# ATmega128RFA1-DevBoard.net
KiCad netlist of a schematic drawn in EAGLE
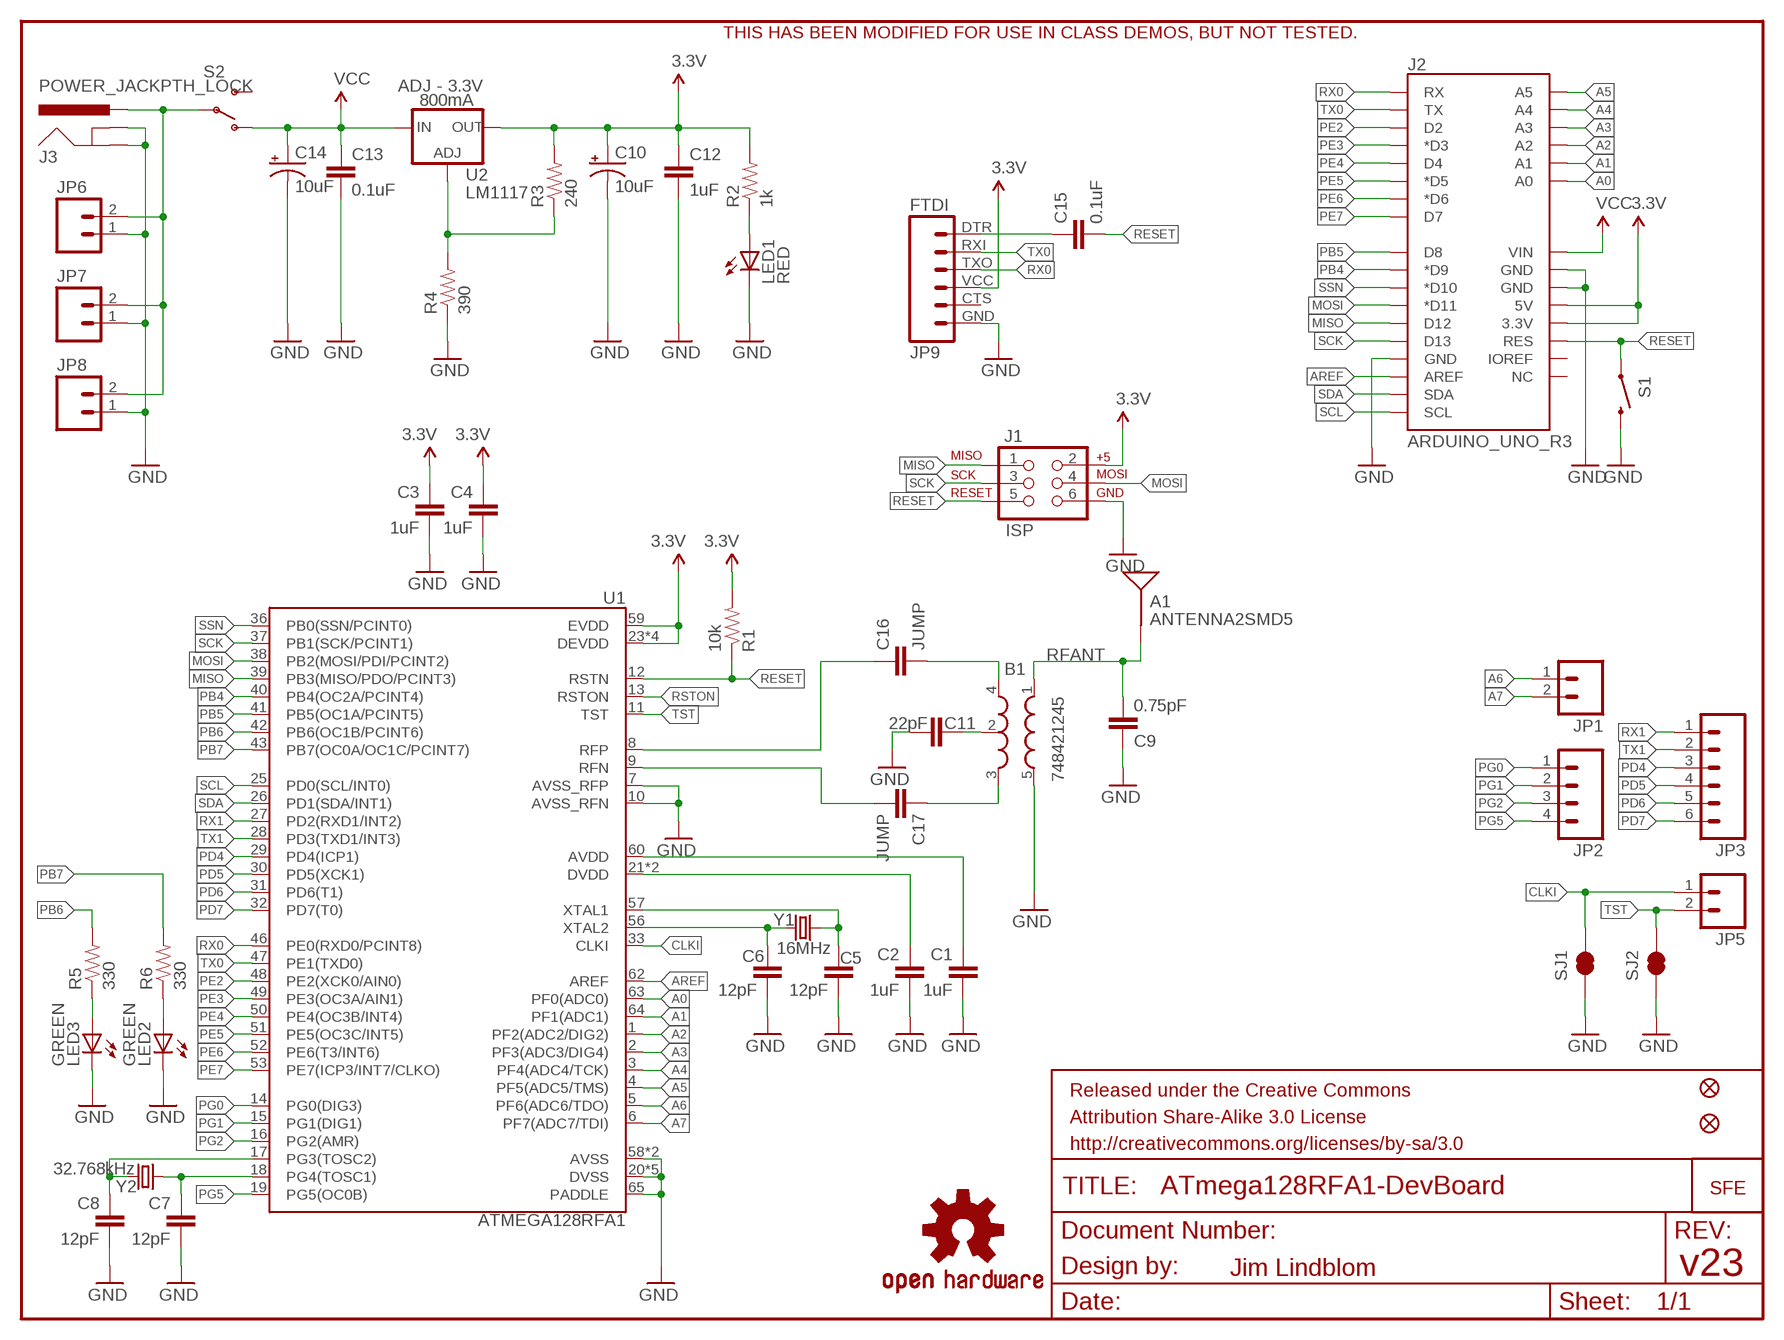
[diagram p0: schematic, sheet 1]

(export (version "E")
  (design (tool "Eeschema 10.0.6"))
  (components
    (comp (ref "A1")
      (value "ANTENNA2SMD5")
      (footprint "eagle-import:ANTENNA-CHIP5")
      (libsource (lib "eagle-import") (part "ANTENNA2SMD5"))
    )
    (comp (ref "B1")
      (value "748421245")
      (footprint "eagle-import:BALUN")
      (libsource (lib "eagle-import") (part "BALUN0805"))
    )
    (comp (ref "C1")
      (value "1uF")
      (footprint "eagle-import:0402-CAP")
      (libsource (lib "eagle-import") (part "CAP0402-CAP"))
    )
    (comp (ref "C2")
      (value "1uF")
      (footprint "eagle-import:0402-CAP")
      (libsource (lib "eagle-import") (part "CAP0402-CAP"))
    )
    (comp (ref "C3")
      (value "1uF")
      (footprint "eagle-import:0402-CAP")
      (libsource (lib "eagle-import") (part "CAP0402-CAP"))
    )
    (comp (ref "C4")
      (value "1uF")
      (footprint "eagle-import:0402-CAP")
      (libsource (lib "eagle-import") (part "CAP0402-CAP"))
    )
    (comp (ref "C5")
      (value "12pF")
      (footprint "eagle-import:0402-CAP")
      (libsource (lib "eagle-import") (part "CAP0402-CAP"))
    )
    (comp (ref "C6")
      (value "12pF")
      (footprint "eagle-import:0402-CAP")
      (libsource (lib "eagle-import") (part "CAP0402-CAP"))
    )
    (comp (ref "C7")
      (value "12pF")
      (footprint "eagle-import:0402-CAP")
      (libsource (lib "eagle-import") (part "CAP0402-CAP"))
    )
    (comp (ref "C8")
      (value "12pF")
      (footprint "eagle-import:0402-CAP")
      (libsource (lib "eagle-import") (part "CAP0402-CAP"))
    )
    (comp (ref "C9")
      (value "0.75pF")
      (footprint "eagle-import:0402-CAP")
      (libsource (lib "eagle-import") (part "CAP0402-CAP"))
    )
    (comp (ref "C10")
      (value "10uF")
      (footprint "eagle-import:EIA3216")
      (libsource (lib "eagle-import") (part "CAP_POL1206"))
    )
    (comp (ref "C11")
      (value "22pF")
      (footprint "eagle-import:0402-CAP")
      (libsource (lib "eagle-import") (part "CAP0402-CAP"))
    )
    (comp (ref "C12")
      (value "1uF")
      (footprint "eagle-import:0402-CAP")
      (libsource (lib "eagle-import") (part "CAP0402-CAP"))
    )
    (comp (ref "C13")
      (value "0.1uF")
      (footprint "eagle-import:0402-CAP")
      (libsource (lib "eagle-import") (part "CAP0402-CAP"))
    )
    (comp (ref "C14")
      (value "10uF")
      (footprint "eagle-import:EIA3216")
      (libsource (lib "eagle-import") (part "CAP_POL1206"))
    )
    (comp (ref "C15")
      (value "0.1uF")
      (footprint "eagle-import:0402-CAP")
      (libsource (lib "eagle-import") (part "CAP0402-CAP"))
    )
    (comp (ref "C16")
      (value "JUMP")
      (footprint "eagle-import:0402-CAP")
      (libsource (lib "eagle-import") (part "CAP0402-CAP"))
    )
    (comp (ref "C17")
      (value "JUMP")
      (footprint "eagle-import:0402-CAP")
      (libsource (lib "eagle-import") (part "CAP0402-CAP"))
    )
    (comp (ref "FID1")
      (value "FIDUCIALUFIDUCIAL")
      (footprint "eagle-import:MICRO-FIDUCIAL")
      (libsource (lib "eagle-import") (part "FIDUCIALUFIDUCIAL"))
    )
    (comp (ref "FID2")
      (value "FIDUCIALUFIDUCIAL")
      (footprint "eagle-import:MICRO-FIDUCIAL")
      (libsource (lib "eagle-import") (part "FIDUCIALUFIDUCIAL"))
    )
    (comp (ref "J1")
      (value "ISP")
      (footprint "eagle-import:2X3-NS")
      (libsource (lib "eagle-import") (part "AVR_SPI_PRG_6NS"))
    )
    (comp (ref "J2")
      (value "ARDUINO_UNO_R3")
      (footprint "eagle-import:ARDUINO_UNO_R3")
      (libsource (lib "eagle-import") (part "ARDUINO_UNO_R3"))
    )
    (comp (ref "J3")
      (value "POWER_JACKPTH_LOCK")
      (footprint "eagle-import:POWER_JACK_PTH_LOCK")
      (libsource (lib "eagle-import") (part "POWER_JACKPTH_LOCK"))
    )
    (comp (ref "JP1")
      (value "M021X02_NO_SILK")
      (footprint "eagle-import:1X02_NO_SILK")
      (libsource (lib "eagle-import") (part "M021X02_NO_SILK"))
    )
    (comp (ref "JP2")
      (value "M041X04_NO_SILK")
      (footprint "eagle-import:1X04_NO_SILK")
      (libsource (lib "eagle-import") (part "M041X04_NO_SILK"))
    )
    (comp (ref "JP3")
      (value "M06SIP-NS")
      (footprint "eagle-import:1X06_NS")
      (libsource (lib "eagle-import") (part "M06SIP-NS"))
    )
    (comp (ref "JP4")
      (value "LOGO-SFENEW")
      (footprint "eagle-import:SFE-NEW-WEBLOGO")
      (libsource (lib "eagle-import") (part "LOGO-SFENEW"))
    )
    (comp (ref "JP5")
      (value "M021X02_NO_SILK")
      (footprint "eagle-import:1X02_NO_SILK")
      (libsource (lib "eagle-import") (part "M021X02_NO_SILK"))
    )
    (comp (ref "JP6")
      (value "M02JST-PTH-2")
      (footprint "eagle-import:JST-2-PTH")
      (libsource (lib "eagle-import") (part "M02JST-PTH-2"))
    )
    (comp (ref "JP7")
      (value "M021X02_NO_SILK")
      (footprint "eagle-import:1X02_NO_SILK")
      (libsource (lib "eagle-import") (part "M021X02_NO_SILK"))
    )
    (comp (ref "JP8")
      (value "M023.5MM-NO_SILK")
      (footprint "eagle-import:SCREWTERMINAL-3.5MM-2-NS")
      (libsource (lib "eagle-import") (part "M023.5MM-NO_SILK"))
    )
    (comp (ref "JP9")
      (value "FTDI")
      (footprint "eagle-import:FTDI_BASIC")
      (libsource (lib "eagle-import") (part "FTDI_BASICPTH"))
    )
    (comp (ref "LED1")
      (value "RED")
      (footprint "eagle-import:LED-0603")
      (libsource (lib "eagle-import") (part "LED0603"))
    )
    (comp (ref "LED2")
      (value "GREEN")
      (footprint "eagle-import:LED-0603")
      (libsource (lib "eagle-import") (part "LED0603"))
    )
    (comp (ref "LED3")
      (value "GREEN")
      (footprint "eagle-import:LED-0603")
      (libsource (lib "eagle-import") (part "LED0603"))
    )
    (comp (ref "R1")
      (value "10k")
      (footprint "eagle-import:0402-RES")
      (libsource (lib "eagle-import") (part "RESISTOR0402-RES"))
    )
    (comp (ref "R2")
      (value "1k")
      (footprint "eagle-import:0402-RES")
      (libsource (lib "eagle-import") (part "RESISTOR0402-RES"))
    )
    (comp (ref "R3")
      (value "240")
      (footprint "eagle-import:0402-RES")
      (libsource (lib "eagle-import") (part "RESISTOR0402-RES"))
    )
    (comp (ref "R4")
      (value "390")
      (footprint "eagle-import:0402-RES")
      (libsource (lib "eagle-import") (part "RESISTOR0402-RES"))
    )
    (comp (ref "R5")
      (value "330")
      (footprint "eagle-import:0402-RES")
      (libsource (lib "eagle-import") (part "RESISTOR0402-RES"))
    )
    (comp (ref "R6")
      (value "330")
      (footprint "eagle-import:0402-RES")
      (libsource (lib "eagle-import") (part "RESISTOR0402-RES"))
    )
    (comp (ref "S1")
      (value "SWITCH-MOMENTARY-2SMD")
      (footprint "eagle-import:TACTILE_SWITCH_SMD")
      (libsource (lib "eagle-import") (part "SWITCH-MOMENTARY-2SMD"))
    )
    (comp (ref "S2")
      (value "SWITCH-SPST-SMD-A")
      (footprint "eagle-import:SWITCH-SPST-SMD-A")
      (libsource (lib "eagle-import") (part "SWITCH-SPST-SMD-A"))
    )
    (comp (ref "SJ1")
      (value "SOLDERJUMPERTRACE")
      (footprint "eagle-import:SJ_2S-TRACE")
      (libsource (lib "eagle-import") (part "SOLDERJUMPERTRACE"))
    )
    (comp (ref "SJ2")
      (value "SOLDERJUMPERTRACE")
      (footprint "eagle-import:SJ_2S-TRACE")
      (libsource (lib "eagle-import") (part "SOLDERJUMPERTRACE"))
    )
    (comp (ref "U$1")
      (value "OSHW-LOGOS")
      (footprint "eagle-import:OSHW-LOGO-S")
      (libsource (lib "eagle-import") (part "OSHW-LOGOS"))
    )
    (comp (ref "U1")
      (value "ATMEGA128RFA1")
      (footprint "eagle-import:QFN-64")
      (libsource (lib "eagle-import") (part "ATMEGA128RFA1"))
    )
    (comp (ref "U2")
      (value "LM1117")
      (footprint "eagle-import:SOT223")
      (libsource (lib "eagle-import") (part "V_REG_317SMD"))
    )
    (comp (ref "Y1")
      (value "16MHz")
      (footprint "eagle-import:CRYSTAL-SMD-5X3")
      (libsource (lib "eagle-import") (part "CRYSTAL5X3"))
    )
    (comp (ref "Y2")
      (value "32.768kHz")
      (footprint "eagle-import:CRYSTAL-32KHZ-SMD")
      (libsource (lib "eagle-import") (part "CRYSTAL32-SMD"))
    )
  )
  (nets
    (net (code "1") (name "/RFANT") (class "Default")
      (node (ref "A1") (pin "FEED") (pinfunction "SIGNAL_FEED") (pintype "bidirectional"))
      (node (ref "B1") (pin "1") (pinfunction "IN_1") (pintype "bidirectional"))
      (node (ref "C9") (pin "2") (pinfunction "2_2") (pintype "passive"))
    )
    (net (code "2") (name "3.3V") (class "Default")
      (node (ref "C10") (pin "A") (pinfunction "+_A") (pintype "passive"))
      (node (ref "C12") (pin "1") (pinfunction "1_1") (pintype "passive"))
      (node (ref "C3") (pin "1") (pinfunction "1_1") (pintype "passive"))
      (node (ref "C4") (pin "1") (pinfunction "1_1") (pintype "passive"))
      (node (ref "J1") (pin "2") (pinfunction "2_2") (pintype "passive"))
      (node (ref "J2") (pin "3.3V") (pinfunction "3.3V_3.3V") (pintype "bidirectional"))
      (node (ref "J2") (pin "5V") (pinfunction "5V_5V") (pintype "bidirectional"))
      (node (ref "JP9") (pin "VCC") (pinfunction "4_VCC") (pintype "passive"))
      (node (ref "R1") (pin "2") (pinfunction "2_2") (pintype "passive"))
      (node (ref "R2") (pin "2") (pinfunction "2_2") (pintype "passive"))
      (node (ref "R3") (pin "2") (pinfunction "2_2") (pintype "passive"))
      (node (ref "U1") (pin "23") (pinfunction "DEVDD_23") (pintype "bidirectional"))
      (node (ref "U1") (pin "34") (pinfunction "DEVDD_34") (pintype "bidirectional"))
      (node (ref "U1") (pin "44") (pinfunction "DEVDD_44") (pintype "bidirectional"))
      (node (ref "U1") (pin "54") (pinfunction "DEVDD_54") (pintype "bidirectional"))
      (node (ref "U1") (pin "59") (pinfunction "EVDD_59") (pintype "bidirectional"))
      (node (ref "U2") (pin "2") (pinfunction "OUT_2") (pintype "output"))
    )
    (net (code "3") (name "A0") (class "Default")
      (node (ref "J2") (pin "A0") (pinfunction "A0_A0") (pintype "bidirectional"))
      (node (ref "U1") (pin "63") (pinfunction "PF0(ADC0)_63") (pintype "bidirectional"))
    )
    (net (code "4") (name "A1") (class "Default")
      (node (ref "J2") (pin "A1") (pinfunction "A1_A1") (pintype "bidirectional"))
      (node (ref "U1") (pin "64") (pinfunction "PF1(ADC1)_64") (pintype "bidirectional"))
    )
    (net (code "5") (name "A2") (class "Default")
      (node (ref "J2") (pin "A2") (pinfunction "A2_A2") (pintype "bidirectional"))
      (node (ref "U1") (pin "1") (pinfunction "PF2(ADC2/DIG2)_1") (pintype "bidirectional"))
    )
    (net (code "6") (name "A3") (class "Default")
      (node (ref "J2") (pin "A3") (pinfunction "A3_A3") (pintype "bidirectional"))
      (node (ref "U1") (pin "2") (pinfunction "PF3(ADC3/DIG4)_2") (pintype "bidirectional"))
    )
    (net (code "7") (name "A4") (class "Default")
      (node (ref "J2") (pin "A4") (pinfunction "A4_A4") (pintype "bidirectional"))
      (node (ref "U1") (pin "3") (pinfunction "PF4(ADC4/TCK)_3") (pintype "bidirectional"))
    )
    (net (code "8") (name "A5") (class "Default")
      (node (ref "J2") (pin "A5") (pinfunction "A5_A5") (pintype "bidirectional"))
      (node (ref "U1") (pin "4") (pinfunction "PF5(ADC5/TMS)_4") (pintype "bidirectional"))
    )
    (net (code "9") (name "A6") (class "Default")
      (node (ref "JP1") (pin "1") (pinfunction "1_1") (pintype "passive"))
      (node (ref "U1") (pin "5") (pinfunction "PF6(ADC6/TDO)_5") (pintype "bidirectional"))
    )
    (net (code "10") (name "A7") (class "Default")
      (node (ref "JP1") (pin "2") (pinfunction "2_2") (pintype "passive"))
      (node (ref "U1") (pin "6") (pinfunction "PF7(ADC7/TDI)_6") (pintype "bidirectional"))
    )
    (net (code "11") (name "AREF") (class "Default")
      (node (ref "J2") (pin "AREF") (pinfunction "AREF_AREF") (pintype "bidirectional"))
      (node (ref "U1") (pin "62") (pinfunction "AREF_62") (pintype "bidirectional"))
    )
    (net (code "12") (name "CLKI") (class "Default")
      (node (ref "JP5") (pin "1") (pinfunction "1_1") (pintype "passive"))
      (node (ref "SJ1") (pin "2") (pinfunction "2_2") (pintype "passive"))
      (node (ref "U1") (pin "33") (pinfunction "CLKI_33") (pintype "bidirectional"))
    )
    (net (code "13") (name "GND") (class "Default")
      (node (ref "B1") (pin "5") (pinfunction "GND_5") (pintype "bidirectional"))
      (node (ref "C1") (pin "2") (pinfunction "2_2") (pintype "passive"))
      (node (ref "C10") (pin "C") (pinfunction "-_C") (pintype "passive"))
      (node (ref "C11") (pin "2") (pinfunction "2_2") (pintype "passive"))
      (node (ref "C12") (pin "2") (pinfunction "2_2") (pintype "passive"))
      (node (ref "C13") (pin "2") (pinfunction "2_2") (pintype "passive"))
      (node (ref "C14") (pin "C") (pinfunction "-_C") (pintype "passive"))
      (node (ref "C2") (pin "2") (pinfunction "2_2") (pintype "passive"))
      (node (ref "C3") (pin "2") (pinfunction "2_2") (pintype "passive"))
      (node (ref "C4") (pin "2") (pinfunction "2_2") (pintype "passive"))
      (node (ref "C5") (pin "2") (pinfunction "2_2") (pintype "passive"))
      (node (ref "C6") (pin "2") (pinfunction "2_2") (pintype "passive"))
      (node (ref "C7") (pin "2") (pinfunction "2_2") (pintype "passive"))
      (node (ref "C8") (pin "2") (pinfunction "2_2") (pintype "passive"))
      (node (ref "C9") (pin "1") (pinfunction "1_1") (pintype "passive"))
      (node (ref "J1") (pin "6") (pinfunction "6_6") (pintype "passive"))
      (node (ref "J2") (pin "GND@0") (pinfunction "GND_GND@0") (pintype "bidirectional"))
      (node (ref "J2") (pin "GND@1") (pinfunction "GND_GND@1") (pintype "bidirectional"))
      (node (ref "J2") (pin "GND@2") (pinfunction "GND_GND@2") (pintype "bidirectional"))
      (node (ref "J3") (pin "GND") (pinfunction "GND_GND") (pintype "bidirectional"))
      (node (ref "J3") (pin "GNDBREAK") (pinfunction "GNDBREAK_GNDBREAK") (pintype "bidirectional"))
      (node (ref "JP6") (pin "1") (pinfunction "1_1") (pintype "passive"))
      (node (ref "JP7") (pin "1") (pinfunction "1_1") (pintype "passive"))
      (node (ref "JP8") (pin "1") (pinfunction "1_1") (pintype "passive"))
      (node (ref "JP9") (pin "GND") (pinfunction "6_GND") (pintype "passive"))
      (node (ref "LED1") (pin "C") (pinfunction "C_C") (pintype "passive"))
      (node (ref "LED2") (pin "C") (pinfunction "C_C") (pintype "passive"))
      (node (ref "LED3") (pin "C") (pinfunction "C_C") (pintype "passive"))
      (node (ref "R4") (pin "1") (pinfunction "1_1") (pintype "passive"))
      (node (ref "S1") (pin "3") (pinfunction "2_3") (pintype "passive"))
      (node (ref "SJ1") (pin "1") (pinfunction "1_1") (pintype "passive"))
      (node (ref "SJ2") (pin "1") (pinfunction "1_1") (pintype "passive"))
      (node (ref "U1") (pin "10") (pinfunction "AVSS_RFN_10") (pintype "bidirectional"))
      (node (ref "U1") (pin "20") (pinfunction "DVSS_20") (pintype "bidirectional"))
      (node (ref "U1") (pin "24") (pinfunction "DVSS_24") (pintype "bidirectional"))
      (node (ref "U1") (pin "35") (pinfunction "DVSS_35") (pintype "bidirectional"))
      (node (ref "U1") (pin "45") (pinfunction "DVSS_45") (pintype "bidirectional"))
      (node (ref "U1") (pin "55") (pinfunction "DVSS_55") (pintype "bidirectional"))
      (node (ref "U1") (pin "58") (pinfunction "AVSS_58") (pintype "bidirectional"))
      (node (ref "U1") (pin "61") (pinfunction "AVSS_61") (pintype "bidirectional"))
      (node (ref "U1") (pin "65") (pinfunction "PADDLE_65") (pintype "bidirectional"))
      (node (ref "U1") (pin "7") (pinfunction "AVSS_RFP_7") (pintype "bidirectional"))
    )
    (net (code "14") (name "MISO") (class "Default")
      (node (ref "J1") (pin "1") (pinfunction "1_1") (pintype "passive"))
      (node (ref "J2") (pin "D12") (pinfunction "D12_D12") (pintype "bidirectional"))
      (node (ref "U1") (pin "39") (pinfunction "PB3(MISO/PDO/PCINT3)_39") (pintype "bidirectional"))
    )
    (net (code "15") (name "MOSI") (class "Default")
      (node (ref "J1") (pin "4") (pinfunction "4_4") (pintype "passive"))
      (node (ref "J2") (pin "D11") (pinfunction "*D11_D11") (pintype "bidirectional"))
      (node (ref "U1") (pin "38") (pinfunction "PB2(MOSI/PDI/PCINT2)_38") (pintype "bidirectional"))
    )
    (net (code "16") (name "Net-(B1-GND-Pad2)") (class "Default")
      (node (ref "B1") (pin "2") (pinfunction "GND_2") (pintype "bidirectional"))
      (node (ref "C11") (pin "1") (pinfunction "1_1") (pintype "passive"))
    )
    (net (code "17") (name "Net-(B1-OUT1)") (class "Default")
      (node (ref "B1") (pin "4") (pinfunction "OUT1_4") (pintype "bidirectional"))
      (node (ref "C16") (pin "2") (pinfunction "2_2") (pintype "passive"))
    )
    (net (code "18") (name "Net-(B1-OUT2)") (class "Default")
      (node (ref "B1") (pin "3") (pinfunction "OUT2_3") (pintype "bidirectional"))
      (node (ref "C17") (pin "1") (pinfunction "1_1") (pintype "passive"))
    )
    (net (code "19") (name "Net-(C2-Pad1)") (class "Default")
      (node (ref "C2") (pin "1") (pinfunction "1_1") (pintype "passive"))
      (node (ref "U1") (pin "21") (pinfunction "DVDD_21") (pintype "bidirectional"))
      (node (ref "U1") (pin "22") (pinfunction "DVDD_22") (pintype "bidirectional"))
    )
    (net (code "20") (name "Net-(JP9-1)") (class "Default")
      (node (ref "C15") (pin "1") (pinfunction "1_1") (pintype "passive"))
      (node (ref "JP9") (pin "DTR") (pinfunction "1_DTR") (pintype "passive"))
    )
    (net (code "21") (name "Net-(LED1-PadA)") (class "Default")
      (node (ref "LED1") (pin "A") (pinfunction "A_A") (pintype "passive"))
      (node (ref "R2") (pin "1") (pinfunction "1_1") (pintype "passive"))
    )
    (net (code "22") (name "Net-(LED2-PadA)") (class "Default")
      (node (ref "LED2") (pin "A") (pinfunction "A_A") (pintype "passive"))
      (node (ref "R6") (pin "1") (pinfunction "1_1") (pintype "passive"))
    )
    (net (code "23") (name "Net-(LED3-PadA)") (class "Default")
      (node (ref "LED3") (pin "A") (pinfunction "A_A") (pintype "passive"))
      (node (ref "R5") (pin "1") (pinfunction "1_1") (pintype "passive"))
    )
    (net (code "24") (name "Net-(S2-P)") (class "Default")
      (node (ref "J3") (pin "PWR") (pinfunction "PWR_PWR") (pintype "bidirectional"))
      (node (ref "JP6") (pin "2") (pinfunction "2_2") (pintype "passive"))
      (node (ref "JP7") (pin "2") (pinfunction "2_2") (pintype "passive"))
      (node (ref "JP8") (pin "2") (pinfunction "2_2") (pintype "passive"))
      (node (ref "S2") (pin "2") (pinfunction "P_2") (pintype "passive"))
    )
    (net (code "25") (name "Net-(U1-AVDD)") (class "Default")
      (node (ref "C1") (pin "1") (pinfunction "1_1") (pintype "passive"))
      (node (ref "U1") (pin "60") (pinfunction "AVDD_60") (pintype "bidirectional"))
    )
    (net (code "26") (name "Net-(U1-PG3(TOSC2))") (class "Default")
      (node (ref "C8") (pin "1") (pinfunction "1_1") (pintype "passive"))
      (node (ref "U1") (pin "17") (pinfunction "PG3(TOSC2)_17") (pintype "bidirectional"))
      (node (ref "Y2") (pin "X2") (pinfunction "2_X2") (pintype "passive"))
    )
    (net (code "27") (name "Net-(U1-PG4(TOSC1))") (class "Default")
      (node (ref "C7") (pin "1") (pinfunction "1_1") (pintype "passive"))
      (node (ref "U1") (pin "18") (pinfunction "PG4(TOSC1)_18") (pintype "bidirectional"))
      (node (ref "Y2") (pin "X1") (pinfunction "1_X1") (pintype "passive"))
    )
    (net (code "28") (name "Net-(U1-RFN)") (class "Default")
      (node (ref "C17") (pin "2") (pinfunction "2_2") (pintype "passive"))
      (node (ref "U1") (pin "9") (pinfunction "RFN_9") (pintype "bidirectional"))
    )
    (net (code "29") (name "Net-(U1-RFP)") (class "Default")
      (node (ref "C16") (pin "1") (pinfunction "1_1") (pintype "passive"))
      (node (ref "U1") (pin "8") (pinfunction "RFP_8") (pintype "bidirectional"))
    )
    (net (code "30") (name "Net-(U1-XTAL1)") (class "Default")
      (node (ref "C5") (pin "1") (pinfunction "1_1") (pintype "passive"))
      (node (ref "U1") (pin "57") (pinfunction "XTAL1_57") (pintype "bidirectional"))
      (node (ref "Y1") (pin "3") (pinfunction "2_3") (pintype "passive"))
    )
    (net (code "31") (name "Net-(U1-XTAL2)") (class "Default")
      (node (ref "C6") (pin "1") (pinfunction "1_1") (pintype "passive"))
      (node (ref "U1") (pin "56") (pinfunction "XTAL2_56") (pintype "bidirectional"))
      (node (ref "Y1") (pin "1") (pinfunction "1_1") (pintype "passive"))
    )
    (net (code "32") (name "Net-(U2-ADJ)") (class "Default")
      (node (ref "R3") (pin "1") (pinfunction "1_1") (pintype "passive"))
      (node (ref "R4") (pin "2") (pinfunction "2_2") (pintype "passive"))
      (node (ref "U2") (pin "1") (pinfunction "ADJ_1") (pintype "input"))
    )
    (net (code "33") (name "PB4") (class "Default")
      (node (ref "J2") (pin "D9") (pinfunction "*D9_D9") (pintype "bidirectional"))
      (node (ref "U1") (pin "40") (pinfunction "PB4(OC2A/PCINT4)_40") (pintype "bidirectional"))
    )
    (net (code "34") (name "PB5") (class "Default")
      (node (ref "J2") (pin "D8") (pinfunction "D8_D8") (pintype "bidirectional"))
      (node (ref "U1") (pin "41") (pinfunction "PB5(OC1A/PCINT5)_41") (pintype "bidirectional"))
    )
    (net (code "35") (name "PB6") (class "Default")
      (node (ref "R5") (pin "2") (pinfunction "2_2") (pintype "passive"))
      (node (ref "U1") (pin "42") (pinfunction "PB6(OC1B/PCINT6)_42") (pintype "bidirectional"))
    )
    (net (code "36") (name "PB7") (class "Default")
      (node (ref "R6") (pin "2") (pinfunction "2_2") (pintype "passive"))
      (node (ref "U1") (pin "43") (pinfunction "PB7(OC0A/OC1C/PCINT7)_43") (pintype "bidirectional"))
    )
    (net (code "37") (name "PD4") (class "Default")
      (node (ref "JP3") (pin "3") (pinfunction "3_3") (pintype "passive"))
      (node (ref "U1") (pin "29") (pinfunction "PD4(ICP1)_29") (pintype "bidirectional"))
    )
    (net (code "38") (name "PD5") (class "Default")
      (node (ref "JP3") (pin "4") (pinfunction "4_4") (pintype "passive"))
      (node (ref "U1") (pin "30") (pinfunction "PD5(XCK1)_30") (pintype "bidirectional"))
    )
    (net (code "39") (name "PD6") (class "Default")
      (node (ref "JP3") (pin "5") (pinfunction "5_5") (pintype "passive"))
      (node (ref "U1") (pin "31") (pinfunction "PD6(T1)_31") (pintype "bidirectional"))
    )
    (net (code "40") (name "PD7") (class "Default")
      (node (ref "JP3") (pin "6") (pinfunction "6_6") (pintype "passive"))
      (node (ref "U1") (pin "32") (pinfunction "PD7(T0)_32") (pintype "bidirectional"))
    )
    (net (code "41") (name "PE2") (class "Default")
      (node (ref "J2") (pin "D2") (pinfunction "D2_D2") (pintype "bidirectional"))
      (node (ref "U1") (pin "48") (pinfunction "PE2(XCK0/AIN0)_48") (pintype "bidirectional"))
    )
    (net (code "42") (name "PE3") (class "Default")
      (node (ref "J2") (pin "D3") (pinfunction "*D3_D3") (pintype "bidirectional"))
      (node (ref "U1") (pin "49") (pinfunction "PE3(OC3A/AIN1)_49") (pintype "bidirectional"))
    )
    (net (code "43") (name "PE4") (class "Default")
      (node (ref "J2") (pin "D4") (pinfunction "D4_D4") (pintype "bidirectional"))
      (node (ref "U1") (pin "50") (pinfunction "PE4(OC3B/INT4)_50") (pintype "bidirectional"))
    )
    (net (code "44") (name "PE5") (class "Default")
      (node (ref "J2") (pin "D5") (pinfunction "*D5_D5") (pintype "bidirectional"))
      (node (ref "U1") (pin "51") (pinfunction "PE5(OC3C/INT5)_51") (pintype "bidirectional"))
    )
    (net (code "45") (name "PE6") (class "Default")
      (node (ref "J2") (pin "D6") (pinfunction "*D6_D6") (pintype "bidirectional"))
      (node (ref "U1") (pin "52") (pinfunction "PE6(T3/INT6)_52") (pintype "bidirectional"))
    )
    (net (code "46") (name "PE7") (class "Default")
      (node (ref "J2") (pin "D7") (pinfunction "D7_D7") (pintype "bidirectional"))
      (node (ref "U1") (pin "53") (pinfunction "PE7(ICP3/INT7/CLKO)_53") (pintype "bidirectional"))
    )
    (net (code "47") (name "PG0") (class "Default")
      (node (ref "JP2") (pin "1") (pinfunction "1_1") (pintype "passive"))
      (node (ref "U1") (pin "14") (pinfunction "PG0(DIG3)_14") (pintype "bidirectional"))
    )
    (net (code "48") (name "PG1") (class "Default")
      (node (ref "JP2") (pin "2") (pinfunction "2_2") (pintype "passive"))
      (node (ref "U1") (pin "15") (pinfunction "PG1(DIG1)_15") (pintype "bidirectional"))
    )
    (net (code "49") (name "PG2") (class "Default")
      (node (ref "JP2") (pin "3") (pinfunction "3_3") (pintype "passive"))
      (node (ref "U1") (pin "16") (pinfunction "PG2(AMR)_16") (pintype "bidirectional"))
    )
    (net (code "50") (name "PG5") (class "Default")
      (node (ref "JP2") (pin "4") (pinfunction "4_4") (pintype "passive"))
      (node (ref "U1") (pin "19") (pinfunction "PG5(OC0B)_19") (pintype "bidirectional"))
    )
    (net (code "51") (name "RESET") (class "Default")
      (node (ref "C15") (pin "2") (pinfunction "2_2") (pintype "passive"))
      (node (ref "J1") (pin "5") (pinfunction "5_5") (pintype "passive"))
      (node (ref "J2") (pin "RES") (pinfunction "RES_RES") (pintype "bidirectional"))
      (node (ref "R1") (pin "1") (pinfunction "1_1") (pintype "passive"))
      (node (ref "S1") (pin "1") (pinfunction "1_1") (pintype "passive"))
      (node (ref "U1") (pin "12") (pinfunction "RSTN_12") (pintype "bidirectional"))
    )
    (net (code "52") (name "RSTON") (class "Default")
      (node (ref "U1") (pin "13") (pinfunction "RSTON_13") (pintype "bidirectional"))
    )
    (net (code "53") (name "RX0") (class "Default")
      (node (ref "J2") (pin "RX") (pinfunction "RX_RX") (pintype "bidirectional"))
      (node (ref "JP9") (pin "TXO") (pinfunction "3_TXO") (pintype "passive"))
      (node (ref "U1") (pin "46") (pinfunction "PE0(RXD0/PCINT8)_46") (pintype "bidirectional"))
    )
    (net (code "54") (name "RX1") (class "Default")
      (node (ref "JP3") (pin "1") (pinfunction "1_1") (pintype "passive"))
      (node (ref "U1") (pin "27") (pinfunction "PD2(RXD1/INT2)_27") (pintype "bidirectional"))
    )
    (net (code "55") (name "SCK") (class "Default")
      (node (ref "J1") (pin "3") (pinfunction "3_3") (pintype "passive"))
      (node (ref "J2") (pin "D13") (pinfunction "D13_D13") (pintype "bidirectional"))
      (node (ref "U1") (pin "37") (pinfunction "PB1(SCK/PCINT1)_37") (pintype "bidirectional"))
    )
    (net (code "56") (name "SCL") (class "Default")
      (node (ref "J2") (pin "SCL") (pinfunction "SCL_SCL") (pintype "bidirectional"))
      (node (ref "U1") (pin "25") (pinfunction "PD0(SCL/INT0)_25") (pintype "bidirectional"))
    )
    (net (code "57") (name "SDA") (class "Default")
      (node (ref "J2") (pin "SDA") (pinfunction "SDA_SDA") (pintype "bidirectional"))
      (node (ref "U1") (pin "26") (pinfunction "PD1(SDA/INT1)_26") (pintype "bidirectional"))
    )
    (net (code "58") (name "SSN") (class "Default")
      (node (ref "J2") (pin "D10") (pinfunction "*D10_D10") (pintype "bidirectional"))
      (node (ref "U1") (pin "36") (pinfunction "PB0(SSN/PCINT0)_36") (pintype "bidirectional"))
    )
    (net (code "59") (name "TST") (class "Default")
      (node (ref "JP5") (pin "2") (pinfunction "2_2") (pintype "passive"))
      (node (ref "SJ2") (pin "2") (pinfunction "2_2") (pintype "passive"))
      (node (ref "U1") (pin "11") (pinfunction "TST_11") (pintype "bidirectional"))
    )
    (net (code "60") (name "TX0") (class "Default")
      (node (ref "J2") (pin "TX") (pinfunction "TX_TX") (pintype "bidirectional"))
      (node (ref "JP9") (pin "RXI") (pinfunction "2_RXI") (pintype "passive"))
      (node (ref "U1") (pin "47") (pinfunction "PE1(TXD0)_47") (pintype "bidirectional"))
    )
    (net (code "61") (name "TX1") (class "Default")
      (node (ref "JP3") (pin "2") (pinfunction "2_2") (pintype "passive"))
      (node (ref "U1") (pin "28") (pinfunction "PD3(TXD1/INT3)_28") (pintype "bidirectional"))
    )
    (net (code "62") (name "VCC") (class "Default")
      (node (ref "C13") (pin "1") (pinfunction "1_1") (pintype "passive"))
      (node (ref "C14") (pin "A") (pinfunction "+_A") (pintype "passive"))
      (node (ref "J2") (pin "VIN") (pinfunction "VIN_VIN") (pintype "bidirectional"))
      (node (ref "S2") (pin "1") (pinfunction "O_1") (pintype "passive"))
      (node (ref "U2") (pin "3") (pinfunction "IN_3") (pintype "input"))
    )
    (net (code "63") (name "unconnected-(J2-PadIOREF)") (class "Default")
      (node (ref "J2") (pin "IOREF") (pinfunction "IOREF_IOREF") (pintype "bidirectional"))
    )
    (net (code "64") (name "unconnected-(J2-PadNC)") (class "Default")
      (node (ref "J2") (pin "NC") (pinfunction "NC_NC") (pintype "bidirectional"))
    )
    (net (code "65") (name "unconnected-(JP9-5-PadCTS)") (class "Default")
      (node (ref "JP9") (pin "CTS") (pinfunction "5_CTS") (pintype "passive"))
    )
    (net (code "66") (name "unconnected-(S2-S-Pad3)") (class "Default")
      (node (ref "S2") (pin "3") (pinfunction "S_3") (pintype "passive"))
    )
  )
)
